# MIDITheremin.net
KiCad netlist of a schematic drawn in EAGLE
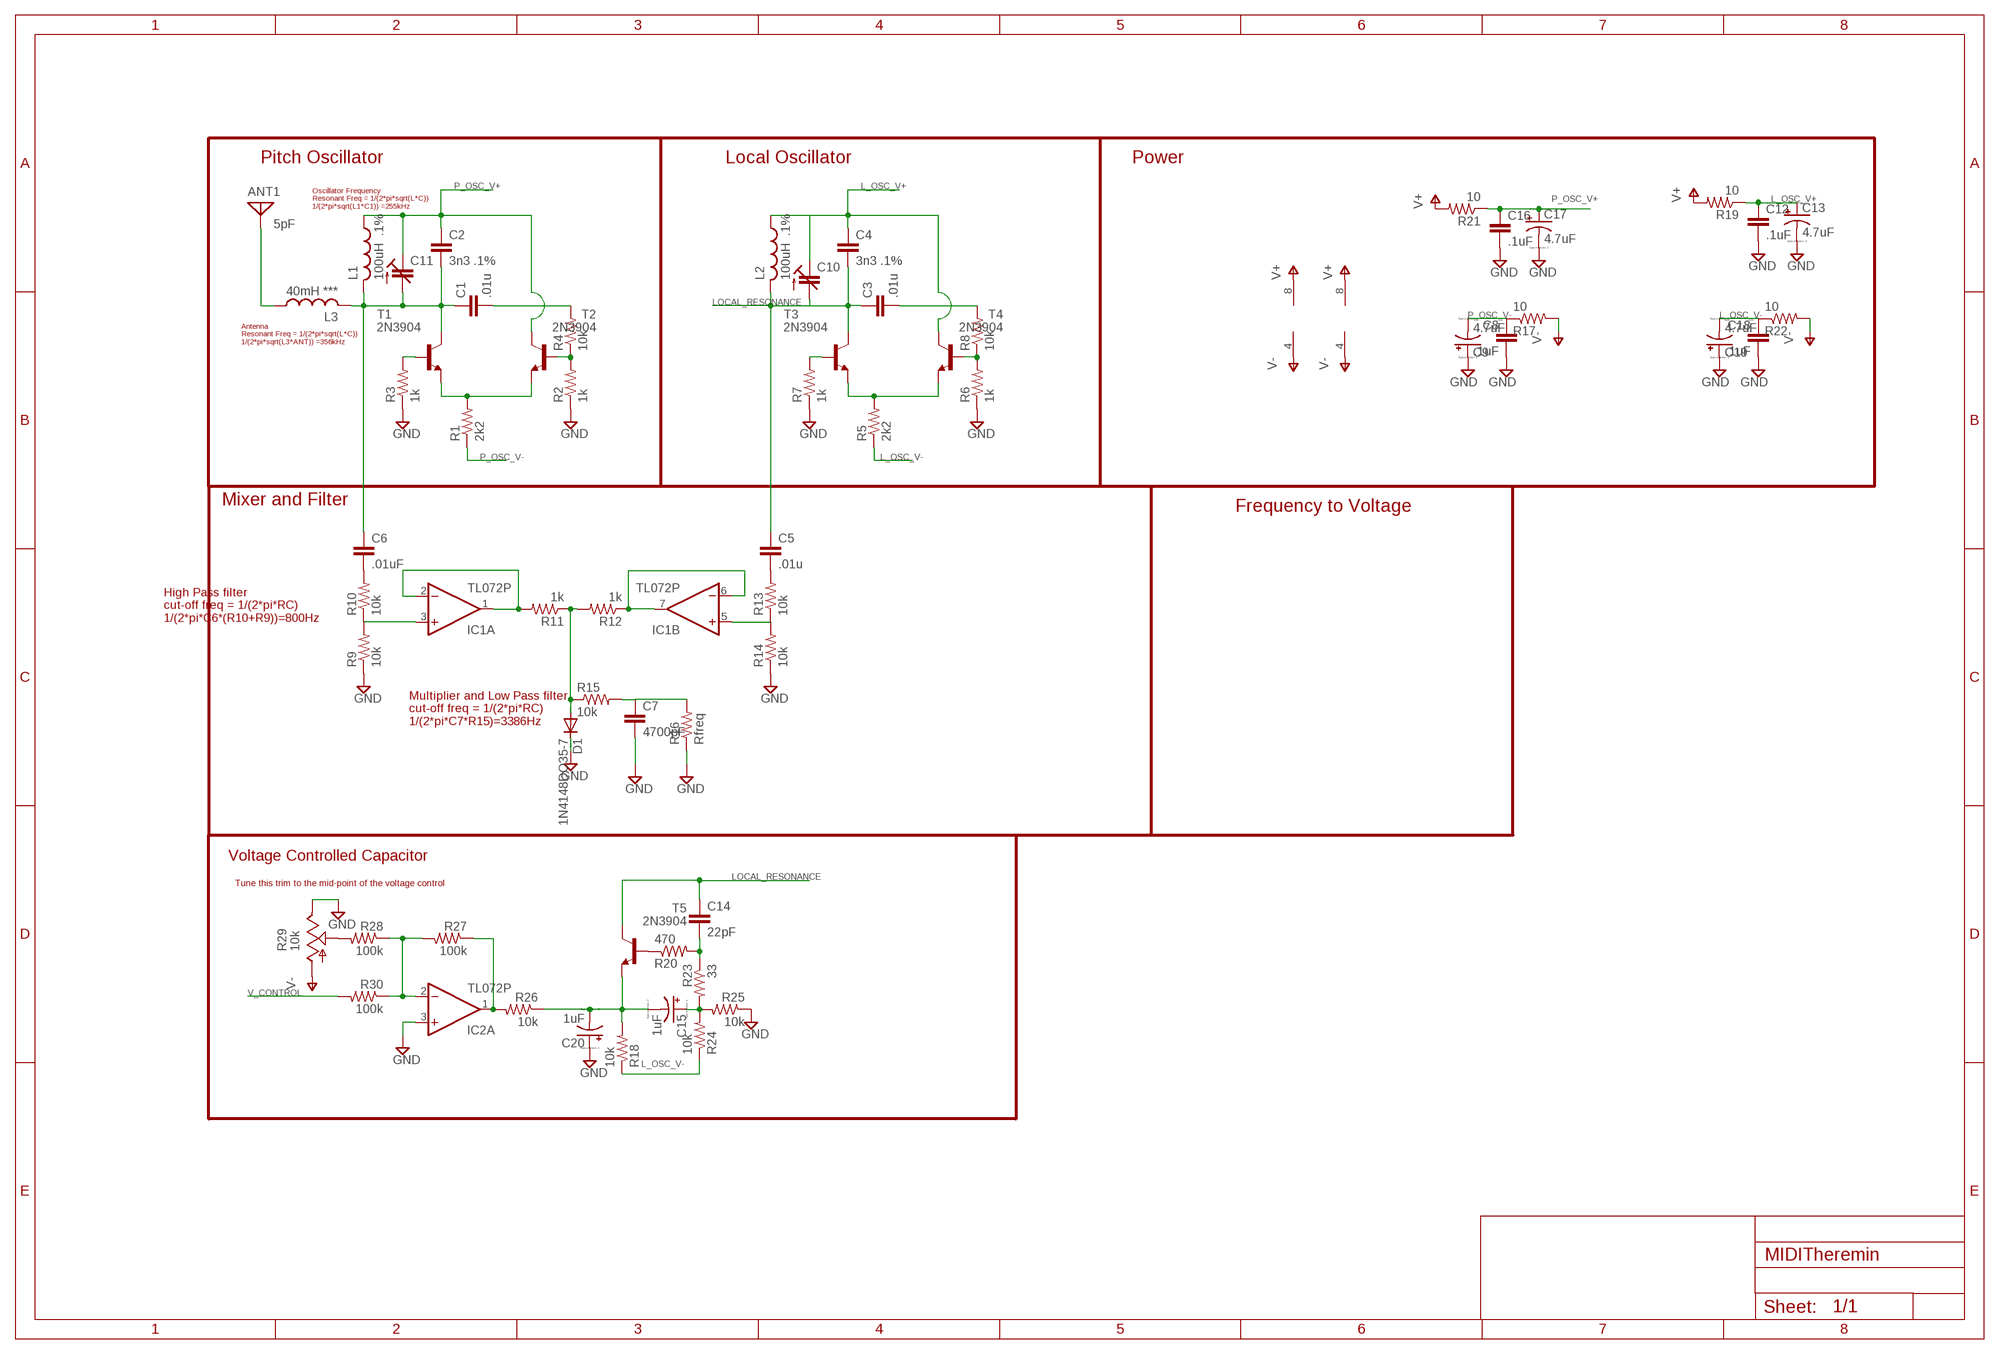
[diagram p0: schematic, sheet 1]

(export (version "E")
  (design (tool "Eeschema 10.0.6"))
  (components
    (comp (ref "ANT1")
      (value "5pF")
      (footprint "eagle-import:PAD-01")
      (libsource (lib "eagle-import") (part "ANTENNA"))
    )
    (comp (ref "C1")
      (value ".01u")
      (footprint "eagle-import:C050-025X075")
      (libsource (lib "eagle-import") (part "C-EU050-025X075"))
    )
    (comp (ref "C2")
      (value "3n3 .1%")
      (footprint "eagle-import:C050-025X075")
      (libsource (lib "eagle-import") (part "C-EU050-025X075"))
    )
    (comp (ref "C3")
      (value ".01u")
      (footprint "eagle-import:C050-025X075")
      (libsource (lib "eagle-import") (part "C-EU050-025X075"))
    )
    (comp (ref "C4")
      (value "3n3 .1%")
      (footprint "eagle-import:C050-025X075")
      (libsource (lib "eagle-import") (part "C-EU050-025X075"))
    )
    (comp (ref "C5")
      (value ".01u")
      (footprint "eagle-import:C050-025X075")
      (libsource (lib "eagle-import") (part "C-EU050-025X075"))
    )
    (comp (ref "C6")
      (value ".01uF")
      (footprint "eagle-import:C050-025X075")
      (libsource (lib "eagle-import") (part "C-EU050-025X075"))
    )
    (comp (ref "C7")
      (value "4700pF")
      (footprint "eagle-import:C050-025X075")
      (libsource (lib "eagle-import") (part "C-EU050-025X075"))
    )
    (comp (ref "C8")
      (value ".1uF")
      (footprint "eagle-import:C050-025X075")
      (libsource (lib "eagle-import") (part "C-EU050-025X075"))
    )
    (comp (ref "C9")
      (value "4.7uF")
      (footprint "eagle-import:E2,5-7")
      (libsource (lib "eagle-import") (part "CPOL-USE2.5-7"))
    )
    (comp (ref "C10")
      (value "C-TRIMM3008")
      (footprint "eagle-import:3008")
      (libsource (lib "eagle-import") (part "C-TRIMM3008"))
    )
    (comp (ref "C11")
      (value "C-TRIMM3008")
      (footprint "eagle-import:3008")
      (libsource (lib "eagle-import") (part "C-TRIMM3008"))
    )
    (comp (ref "C12")
      (value ".1uF")
      (footprint "eagle-import:C050-025X075")
      (libsource (lib "eagle-import") (part "C-EU050-025X075"))
    )
    (comp (ref "C13")
      (value "4.7uF")
      (footprint "eagle-import:E2,5-7")
      (libsource (lib "eagle-import") (part "CPOL-USE2.5-7"))
    )
    (comp (ref "C14")
      (value "22pF")
      (footprint "eagle-import:C050-025X075")
      (libsource (lib "eagle-import") (part "C-EU050-025X075"))
    )
    (comp (ref "C15")
      (value "1uF")
      (footprint "eagle-import:E2,5-7")
      (libsource (lib "eagle-import") (part "CPOL-USE2.5-7"))
    )
    (comp (ref "C16")
      (value ".1uF")
      (footprint "eagle-import:C050-025X075")
      (libsource (lib "eagle-import") (part "C-EU050-025X075"))
    )
    (comp (ref "C17")
      (value "4.7uF")
      (footprint "eagle-import:E2,5-7")
      (libsource (lib "eagle-import") (part "CPOL-USE2.5-7"))
    )
    (comp (ref "C18")
      (value ".1uF")
      (footprint "eagle-import:C050-025X075")
      (libsource (lib "eagle-import") (part "C-EU050-025X075"))
    )
    (comp (ref "C19")
      (value "4.7uF")
      (footprint "eagle-import:E2,5-7")
      (libsource (lib "eagle-import") (part "CPOL-USE2.5-7"))
    )
    (comp (ref "C20")
      (value "1uF")
      (footprint "eagle-import:E2,5-7")
      (libsource (lib "eagle-import") (part "CPOL-USE2.5-7"))
    )
    (comp (ref "D1")
      (value "1N4148DO35-7")
      (footprint "eagle-import:DO35-7")
      (libsource (lib "eagle-import") (part "1N4148DO35-7"))
    )
    (comp (ref "IC1")
      (value "TL072P")
      (footprint "eagle-import:DIL08")
      (libsource (lib "eagle-import") (part "TL072P"))
    )
    (comp (ref "IC2")
      (value "TL072P")
      (footprint "eagle-import:DIL08")
      (libsource (lib "eagle-import") (part "TL072P"))
    )
    (comp (ref "L1")
      (value "100uH .1%")
      (footprint "eagle-import:0207_2V")
      (libsource (lib "eagle-import") (part "L-US0207/2V"))
    )
    (comp (ref "L2")
      (value "100uH .1%")
      (footprint "eagle-import:0207_2V")
      (libsource (lib "eagle-import") (part "L-US0207/2V"))
    )
    (comp (ref "L3")
      (value "40mH ***")
      (footprint "eagle-import:0207_2V")
      (libsource (lib "eagle-import") (part "L-US0207/2V"))
    )
    (comp (ref "R1")
      (value "2k2")
      (footprint "eagle-import:0411V")
      (libsource (lib "eagle-import") (part "R-US_0411/3V"))
    )
    (comp (ref "R2")
      (value "1k")
      (footprint "eagle-import:0411V")
      (libsource (lib "eagle-import") (part "R-US_0411/3V"))
    )
    (comp (ref "R3")
      (value "1k")
      (footprint "eagle-import:0411V")
      (libsource (lib "eagle-import") (part "R-US_0411/3V"))
    )
    (comp (ref "R4")
      (value "10k")
      (footprint "eagle-import:0411V")
      (libsource (lib "eagle-import") (part "R-US_0411/3V"))
    )
    (comp (ref "R5")
      (value "2k2")
      (footprint "eagle-import:0411V")
      (libsource (lib "eagle-import") (part "R-US_0411/3V"))
    )
    (comp (ref "R6")
      (value "1k")
      (footprint "eagle-import:0411V")
      (libsource (lib "eagle-import") (part "R-US_0411/3V"))
    )
    (comp (ref "R7")
      (value "1k")
      (footprint "eagle-import:0411V")
      (libsource (lib "eagle-import") (part "R-US_0411/3V"))
    )
    (comp (ref "R8")
      (value "10k")
      (footprint "eagle-import:0411V")
      (libsource (lib "eagle-import") (part "R-US_0411/3V"))
    )
    (comp (ref "R9")
      (value "10k")
      (footprint "eagle-import:0411V")
      (libsource (lib "eagle-import") (part "R-US_0411/3V"))
    )
    (comp (ref "R10")
      (value "10k")
      (footprint "eagle-import:0411V")
      (libsource (lib "eagle-import") (part "R-US_0411/3V"))
    )
    (comp (ref "R11")
      (value "1k")
      (footprint "eagle-import:0411V")
      (libsource (lib "eagle-import") (part "R-US_0411/3V"))
    )
    (comp (ref "R12")
      (value "1k")
      (footprint "eagle-import:0411V")
      (libsource (lib "eagle-import") (part "R-US_0411/3V"))
    )
    (comp (ref "R13")
      (value "10k")
      (footprint "eagle-import:0411V")
      (libsource (lib "eagle-import") (part "R-US_0411/3V"))
    )
    (comp (ref "R14")
      (value "10k")
      (footprint "eagle-import:0411V")
      (libsource (lib "eagle-import") (part "R-US_0411/3V"))
    )
    (comp (ref "R15")
      (value "10k")
      (footprint "eagle-import:0411V")
      (libsource (lib "eagle-import") (part "R-US_0411/3V"))
    )
    (comp (ref "R16")
      (value "Rfreq")
      (footprint "eagle-import:0411V")
      (libsource (lib "eagle-import") (part "R-US_0411/3V"))
    )
    (comp (ref "R17")
      (value "10")
      (footprint "eagle-import:0411V")
      (libsource (lib "eagle-import") (part "R-US_0411/3V"))
    )
    (comp (ref "R18")
      (value "10k")
      (footprint "eagle-import:0411V")
      (libsource (lib "eagle-import") (part "R-US_0411/3V"))
    )
    (comp (ref "R19")
      (value "10")
      (footprint "eagle-import:0411V")
      (libsource (lib "eagle-import") (part "R-US_0411/3V"))
    )
    (comp (ref "R20")
      (value "470")
      (footprint "eagle-import:0411V")
      (libsource (lib "eagle-import") (part "R-US_0411/3V"))
    )
    (comp (ref "R21")
      (value "10")
      (footprint "eagle-import:0411V")
      (libsource (lib "eagle-import") (part "R-US_0411/3V"))
    )
    (comp (ref "R22")
      (value "10")
      (footprint "eagle-import:0411V")
      (libsource (lib "eagle-import") (part "R-US_0411/3V"))
    )
    (comp (ref "R23")
      (value "33")
      (footprint "eagle-import:0411V")
      (libsource (lib "eagle-import") (part "R-US_0411/3V"))
    )
    (comp (ref "R24")
      (value "10k")
      (footprint "eagle-import:0411V")
      (libsource (lib "eagle-import") (part "R-US_0411/3V"))
    )
    (comp (ref "R25")
      (value "10k")
      (footprint "eagle-import:0411V")
      (libsource (lib "eagle-import") (part "R-US_0411/3V"))
    )
    (comp (ref "R26")
      (value "10k")
      (footprint "eagle-import:0411V")
      (libsource (lib "eagle-import") (part "R-US_0411/3V"))
    )
    (comp (ref "R27")
      (value "100k")
      (footprint "eagle-import:0411V")
      (libsource (lib "eagle-import") (part "R-US_0411/3V"))
    )
    (comp (ref "R28")
      (value "100k")
      (footprint "eagle-import:0411V")
      (libsource (lib "eagle-import") (part "R-US_0411/3V"))
    )
    (comp (ref "R29")
      (value "10k")
      (footprint "eagle-import:B64Y")
      (libsource (lib "eagle-import") (part "TRIM_US-B64Y"))
    )
    (comp (ref "R30")
      (value "100k")
      (footprint "eagle-import:0411V")
      (libsource (lib "eagle-import") (part "R-US_0411/3V"))
    )
    (comp (ref "T1")
      (value "2N3904")
      (footprint "eagle-import:TO92")
      (libsource (lib "eagle-import") (part "2N3904"))
    )
    (comp (ref "T2")
      (value "2N3904")
      (footprint "eagle-import:TO92")
      (libsource (lib "eagle-import") (part "2N3904"))
    )
    (comp (ref "T3")
      (value "2N3904")
      (footprint "eagle-import:TO92")
      (libsource (lib "eagle-import") (part "2N3904"))
    )
    (comp (ref "T4")
      (value "2N3904")
      (footprint "eagle-import:TO92")
      (libsource (lib "eagle-import") (part "2N3904"))
    )
    (comp (ref "T5")
      (value "2N3904")
      (footprint "eagle-import:TO92")
      (libsource (lib "eagle-import") (part "2N3904"))
    )
  )
  (nets
    (net (code "1") (name "/LOCAL_RESONANCE") (class "Default")
      (node (ref "C10") (pin "-") (pinfunction "A_-") (pintype "passive"))
      (node (ref "C14") (pin "1") (pinfunction "1_1") (pintype "passive"))
      (node (ref "C3") (pin "1") (pinfunction "1_1") (pintype "passive"))
      (node (ref "C4") (pin "2") (pinfunction "2_2") (pintype "passive"))
      (node (ref "C5") (pin "1") (pinfunction "1_1") (pintype "passive"))
      (node (ref "L2") (pin "2") (pinfunction "2_2") (pintype "passive"))
      (node (ref "T3") (pin "1") (pinfunction "C_1") (pintype "passive"))
      (node (ref "T5") (pin "1") (pinfunction "C_1") (pintype "passive"))
    )
    (net (code "2") (name "/L_OSC_V+") (class "Default")
      (node (ref "C10") (pin "+") (pinfunction "E_+") (pintype "passive"))
      (node (ref "C12") (pin "1") (pinfunction "1_1") (pintype "passive"))
      (node (ref "C13") (pin "+") (pinfunction "+_+") (pintype "passive"))
      (node (ref "C4") (pin "1") (pinfunction "1_1") (pintype "passive"))
      (node (ref "L2") (pin "1") (pinfunction "1_1") (pintype "passive"))
      (node (ref "R19") (pin "1") (pinfunction "1_1") (pintype "passive"))
      (node (ref "T4") (pin "1") (pinfunction "C_1") (pintype "passive"))
    )
    (net (code "3") (name "/L_OSC_V-") (class "Default")
      (node (ref "C18") (pin "1") (pinfunction "1_1") (pintype "passive"))
      (node (ref "C19") (pin "-") (pinfunction "-_-") (pintype "passive"))
      (node (ref "R18") (pin "1") (pinfunction "1_1") (pintype "passive"))
      (node (ref "R22") (pin "1") (pinfunction "1_1") (pintype "passive"))
      (node (ref "R24") (pin "1") (pinfunction "1_1") (pintype "passive"))
      (node (ref "R5") (pin "1") (pinfunction "1_1") (pintype "passive"))
    )
    (net (code "4") (name "/P_OSC_V+") (class "Default")
      (node (ref "C11") (pin "+") (pinfunction "E_+") (pintype "passive"))
      (node (ref "C16") (pin "1") (pinfunction "1_1") (pintype "passive"))
      (node (ref "C17") (pin "+") (pinfunction "+_+") (pintype "passive"))
      (node (ref "C2") (pin "1") (pinfunction "1_1") (pintype "passive"))
      (node (ref "L1") (pin "1") (pinfunction "1_1") (pintype "passive"))
      (node (ref "R21") (pin "1") (pinfunction "1_1") (pintype "passive"))
      (node (ref "T2") (pin "1") (pinfunction "C_1") (pintype "passive"))
    )
    (net (code "5") (name "/P_OSC_V-") (class "Default")
      (node (ref "C8") (pin "1") (pinfunction "1_1") (pintype "passive"))
      (node (ref "C9") (pin "-") (pinfunction "-_-") (pintype "passive"))
      (node (ref "R1") (pin "1") (pinfunction "1_1") (pintype "passive"))
      (node (ref "R17") (pin "1") (pinfunction "1_1") (pintype "passive"))
    )
    (net (code "6") (name "/V_CONTROL") (class "Default")
      (node (ref "R30") (pin "2") (pinfunction "2_2") (pintype "passive"))
    )
    (net (code "7") (name "GND") (class "Default")
      (node (ref "C12") (pin "2") (pinfunction "2_2") (pintype "passive"))
      (node (ref "C13") (pin "-") (pinfunction "-_-") (pintype "passive"))
      (node (ref "C16") (pin "2") (pinfunction "2_2") (pintype "passive"))
      (node (ref "C17") (pin "-") (pinfunction "-_-") (pintype "passive"))
      (node (ref "C18") (pin "2") (pinfunction "2_2") (pintype "passive"))
      (node (ref "C19") (pin "+") (pinfunction "+_+") (pintype "passive"))
      (node (ref "C20") (pin "+") (pinfunction "+_+") (pintype "passive"))
      (node (ref "C7") (pin "2") (pinfunction "2_2") (pintype "passive"))
      (node (ref "C8") (pin "2") (pinfunction "2_2") (pintype "passive"))
      (node (ref "C9") (pin "+") (pinfunction "+_+") (pintype "passive"))
      (node (ref "D1") (pin "C") (pinfunction "C_C") (pintype "passive"))
      (node (ref "IC2") (pin "3") (pinfunction "+IN_3") (pintype "input"))
      (node (ref "R14") (pin "1") (pinfunction "1_1") (pintype "passive"))
      (node (ref "R16") (pin "1") (pinfunction "1_1") (pintype "passive"))
      (node (ref "R2") (pin "1") (pinfunction "1_1") (pintype "passive"))
      (node (ref "R25") (pin "1") (pinfunction "1_1") (pintype "passive"))
      (node (ref "R29") (pin "E") (pinfunction "E_E") (pintype "passive"))
      (node (ref "R3") (pin "1") (pinfunction "1_1") (pintype "passive"))
      (node (ref "R6") (pin "1") (pinfunction "1_1") (pintype "passive"))
      (node (ref "R7") (pin "1") (pinfunction "1_1") (pintype "passive"))
      (node (ref "R9") (pin "1") (pinfunction "1_1") (pintype "passive"))
    )
    (net (code "8") (name "Net-(ANT1-Pad1)") (class "Default")
      (node (ref "ANT1") (pin "1") (pinfunction "1_1") (pintype "output"))
      (node (ref "L3") (pin "1") (pinfunction "1_1") (pintype "passive"))
    )
    (net (code "9") (name "Net-(C1-Pad2)") (class "Default")
      (node (ref "C1") (pin "2") (pinfunction "2_2") (pintype "passive"))
      (node (ref "R4") (pin "2") (pinfunction "2_2") (pintype "passive"))
    )
    (net (code "10") (name "Net-(C3-Pad2)") (class "Default")
      (node (ref "C3") (pin "2") (pinfunction "2_2") (pintype "passive"))
      (node (ref "R8") (pin "2") (pinfunction "2_2") (pintype "passive"))
    )
    (net (code "11") (name "Net-(C5-Pad2)") (class "Default")
      (node (ref "C5") (pin "2") (pinfunction "2_2") (pintype "passive"))
      (node (ref "R13") (pin "2") (pinfunction "2_2") (pintype "passive"))
    )
    (net (code "12") (name "Net-(C6-Pad2)") (class "Default")
      (node (ref "C6") (pin "2") (pinfunction "2_2") (pintype "passive"))
      (node (ref "R10") (pin "2") (pinfunction "2_2") (pintype "passive"))
    )
    (net (code "13") (name "Net-(C7-Pad1)") (class "Default")
      (node (ref "C7") (pin "1") (pinfunction "1_1") (pintype "passive"))
      (node (ref "R15") (pin "2") (pinfunction "2_2") (pintype "passive"))
      (node (ref "R16") (pin "2") (pinfunction "2_2") (pintype "passive"))
    )
    (net (code "14") (name "Net-(C11-A)") (class "Default")
      (node (ref "C1") (pin "1") (pinfunction "1_1") (pintype "passive"))
      (node (ref "C11") (pin "-") (pinfunction "A_-") (pintype "passive"))
      (node (ref "C2") (pin "2") (pinfunction "2_2") (pintype "passive"))
      (node (ref "C6") (pin "1") (pinfunction "1_1") (pintype "passive"))
      (node (ref "L1") (pin "2") (pinfunction "2_2") (pintype "passive"))
      (node (ref "L3") (pin "2") (pinfunction "2_2") (pintype "passive"))
      (node (ref "T1") (pin "1") (pinfunction "C_1") (pintype "passive"))
    )
    (net (code "15") (name "Net-(C14-Pad2)") (class "Default")
      (node (ref "C14") (pin "2") (pinfunction "2_2") (pintype "passive"))
      (node (ref "R20") (pin "2") (pinfunction "2_2") (pintype "passive"))
      (node (ref "R23") (pin "1") (pinfunction "1_1") (pintype "passive"))
    )
    (net (code "16") (name "Net-(C15-Pad+)") (class "Default")
      (node (ref "C15") (pin "+") (pinfunction "+_+") (pintype "passive"))
      (node (ref "R23") (pin "2") (pinfunction "2_2") (pintype "passive"))
      (node (ref "R24") (pin "2") (pinfunction "2_2") (pintype "passive"))
      (node (ref "R25") (pin "2") (pinfunction "2_2") (pintype "passive"))
    )
    (net (code "17") (name "Net-(D1-PadA)") (class "Default")
      (node (ref "D1") (pin "A") (pinfunction "A_A") (pintype "passive"))
      (node (ref "R11") (pin "1") (pinfunction "1_1") (pintype "passive"))
      (node (ref "R12") (pin "2") (pinfunction "2_2") (pintype "passive"))
      (node (ref "R15") (pin "1") (pinfunction "1_1") (pintype "passive"))
    )
    (net (code "18") (name "Net-(IC1A-+IN)") (class "Default")
      (node (ref "IC1") (pin "3") (pinfunction "+IN_3") (pintype "input"))
      (node (ref "R10") (pin "1") (pinfunction "1_1") (pintype "passive"))
      (node (ref "R9") (pin "2") (pinfunction "2_2") (pintype "passive"))
    )
    (net (code "19") (name "Net-(IC1A--IN)") (class "Default")
      (node (ref "IC1") (pin "1") (pinfunction "OUT_1") (pintype "output"))
      (node (ref "IC1") (pin "2") (pinfunction "-IN_2") (pintype "input"))
      (node (ref "R11") (pin "2") (pinfunction "2_2") (pintype "passive"))
    )
    (net (code "20") (name "Net-(IC1B-+IN)") (class "Default")
      (node (ref "IC1") (pin "5") (pinfunction "+IN_5") (pintype "input"))
      (node (ref "R13") (pin "1") (pinfunction "1_1") (pintype "passive"))
      (node (ref "R14") (pin "2") (pinfunction "2_2") (pintype "passive"))
    )
    (net (code "21") (name "Net-(IC1B--IN)") (class "Default")
      (node (ref "IC1") (pin "6") (pinfunction "-IN_6") (pintype "input"))
      (node (ref "IC1") (pin "7") (pinfunction "OUT_7") (pintype "output"))
      (node (ref "R12") (pin "1") (pinfunction "1_1") (pintype "passive"))
    )
    (net (code "22") (name "Net-(IC2A--IN)") (class "Default")
      (node (ref "IC2") (pin "2") (pinfunction "-IN_2") (pintype "input"))
      (node (ref "R27") (pin "2") (pinfunction "2_2") (pintype "passive"))
      (node (ref "R28") (pin "1") (pinfunction "1_1") (pintype "passive"))
      (node (ref "R30") (pin "1") (pinfunction "1_1") (pintype "passive"))
    )
    (net (code "23") (name "Net-(IC2A-OUT)") (class "Default")
      (node (ref "IC2") (pin "1") (pinfunction "OUT_1") (pintype "output"))
      (node (ref "R26") (pin "2") (pinfunction "2_2") (pintype "passive"))
      (node (ref "R27") (pin "1") (pinfunction "1_1") (pintype "passive"))
    )
    (net (code "24") (name "Net-(R28-Pad2)") (class "Default")
      (node (ref "R28") (pin "2") (pinfunction "2_2") (pintype "passive"))
      (node (ref "R29") (pin "S") (pinfunction "S_S") (pintype "passive"))
    )
    (net (code "25") (name "Net-(T1-B)") (class "Default")
      (node (ref "R3") (pin "2") (pinfunction "2_2") (pintype "passive"))
      (node (ref "T1") (pin "2") (pinfunction "B_2") (pintype "passive"))
    )
    (net (code "26") (name "Net-(T1-E)") (class "Default")
      (node (ref "R1") (pin "2") (pinfunction "2_2") (pintype "passive"))
      (node (ref "T1") (pin "3") (pinfunction "E_3") (pintype "passive"))
      (node (ref "T2") (pin "3") (pinfunction "E_3") (pintype "passive"))
    )
    (net (code "27") (name "Net-(T2-B)") (class "Default")
      (node (ref "R2") (pin "2") (pinfunction "2_2") (pintype "passive"))
      (node (ref "R4") (pin "1") (pinfunction "1_1") (pintype "passive"))
      (node (ref "T2") (pin "2") (pinfunction "B_2") (pintype "passive"))
    )
    (net (code "28") (name "Net-(T3-B)") (class "Default")
      (node (ref "R7") (pin "2") (pinfunction "2_2") (pintype "passive"))
      (node (ref "T3") (pin "2") (pinfunction "B_2") (pintype "passive"))
    )
    (net (code "29") (name "Net-(T3-E)") (class "Default")
      (node (ref "R5") (pin "2") (pinfunction "2_2") (pintype "passive"))
      (node (ref "T3") (pin "3") (pinfunction "E_3") (pintype "passive"))
      (node (ref "T4") (pin "3") (pinfunction "E_3") (pintype "passive"))
    )
    (net (code "30") (name "Net-(T4-B)") (class "Default")
      (node (ref "R6") (pin "2") (pinfunction "2_2") (pintype "passive"))
      (node (ref "R8") (pin "1") (pinfunction "1_1") (pintype "passive"))
      (node (ref "T4") (pin "2") (pinfunction "B_2") (pintype "passive"))
    )
    (net (code "31") (name "Net-(T5-B)") (class "Default")
      (node (ref "R20") (pin "1") (pinfunction "1_1") (pintype "passive"))
      (node (ref "T5") (pin "2") (pinfunction "B_2") (pintype "passive"))
    )
    (net (code "32") (name "Net-(T5-E)") (class "Default")
      (node (ref "C15") (pin "-") (pinfunction "-_-") (pintype "passive"))
      (node (ref "C20") (pin "-") (pinfunction "-_-") (pintype "passive"))
      (node (ref "R18") (pin "2") (pinfunction "2_2") (pintype "passive"))
      (node (ref "R26") (pin "1") (pinfunction "1_1") (pintype "passive"))
      (node (ref "T5") (pin "3") (pinfunction "E_3") (pintype "passive"))
    )
    (net (code "33") (name "V+") (class "Default")
      (node (ref "IC1") (pin "8") (pinfunction "V+_8") (pintype "power_in"))
      (node (ref "IC2") (pin "8") (pinfunction "V+_8") (pintype "power_in"))
      (node (ref "R19") (pin "2") (pinfunction "2_2") (pintype "passive"))
      (node (ref "R21") (pin "2") (pinfunction "2_2") (pintype "passive"))
    )
    (net (code "34") (name "V-") (class "Default")
      (node (ref "IC1") (pin "4") (pinfunction "V-_4") (pintype "power_in"))
      (node (ref "IC2") (pin "4") (pinfunction "V-_4") (pintype "power_in"))
      (node (ref "R17") (pin "2") (pinfunction "2_2") (pintype "passive"))
      (node (ref "R22") (pin "2") (pinfunction "2_2") (pintype "passive"))
      (node (ref "R29") (pin "A") (pinfunction "A_A") (pintype "passive"))
    )
  )
)
